# On-Screen-Display.net
KiCad netlist of a schematic drawn in Altium Designer
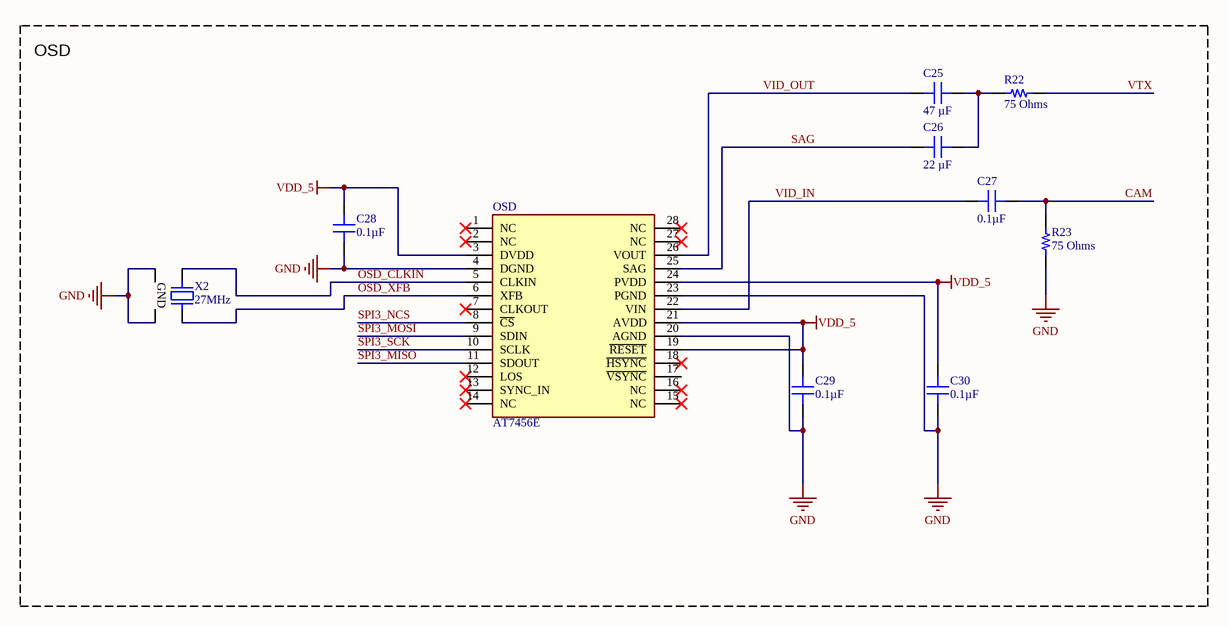
[diagram p0: On-Screen-Display.SchDoc]

(export (version "E")
  (design (tool "Eeschema 10.0.6"))
  (components
    (comp (ref "C25")
      (value "47 µF")
      (footprint "CAP 0603_1608")
      (description "CAP CER 47UF 6.3V X5R 0603")
      (fields
        (field (name "PART NUMBER") "GRM188R60J476ME15D")
        (field (name "MANUFACTURER") "Murata Electronics")
      )
      (libsource (lib "Celestial Altium Library - altium_library") (part "Capacitor"))
    )
    (comp (ref "C26")
      (value "22 µF")
      (footprint "CAP 0603_1608")
      (description "CAP CER 22UF 6.3V X5R 0603")
      (fields
        (field (name "PART NUMBER") "GRM186R60J226ME15D")
        (field (name "MANUFACTURER") "Murata Electronics")
      )
      (libsource (lib "Celestial Altium Library - altium_library") (part "Capacitor"))
    )
    (comp (ref "C27")
      (value "0.1µF")
      (footprint "CAP 0603_1608")
      (description "CAP CER 0.1UF 25V X7R 0603")
      (fields (field (name "PART NUMBER") "06033C104JAT4A") (field (name "MANUFACTURER") "AVX Corporation"))
      (libsource (lib "Celestial Altium Library - altium_library") (part "Capacitor"))
    )
    (comp (ref "C28")
      (value "0.1µF")
      (footprint "CAP 0603_1608")
      (description "CAP CER 0.1UF 25V X7R 0603")
      (fields (field (name "PART NUMBER") "06033C104JAT4A") (field (name "MANUFACTURER") "AVX Corporation"))
      (libsource (lib "Celestial Altium Library - altium_library") (part "Capacitor"))
    )
    (comp (ref "C29")
      (value "0.1µF")
      (footprint "CAP 0603_1608")
      (description "CAP CER 0.1UF 25V X7R 0603")
      (fields (field (name "PART NUMBER") "06033C104JAT4A") (field (name "MANUFACTURER") "AVX Corporation"))
      (libsource (lib "Celestial Altium Library - altium_library") (part "Capacitor"))
    )
    (comp (ref "C30")
      (value "0.1µF")
      (footprint "CAP 0603_1608")
      (description "CAP CER 0.1UF 25V X7R 0603")
      (fields (field (name "PART NUMBER") "06033C104JAT4A") (field (name "MANUFACTURER") "AVX Corporation"))
      (libsource (lib "Celestial Altium Library - altium_library") (part "Capacitor"))
    )
    (comp (ref "OSD")
      (value "AT7456E")
      (footprint "SamacSys:SOP65P640X120-29N")
      (description "Integrated Circuit")
      (libsource (lib "SamacSys") (part "AT7456E"))
    )
    (comp (ref "R22")
      (value "75 Ohms")
      (footprint "RES 0603_1608")
      (description "RES 75 OHM 1% 1/8W 0603")
      (fields
        (field (name "PART NUMBER") "RNCP0603FTD75R0")
        (field (name "MANUFACTURER") "Stackpole Electronics Inc")
      )
      (libsource (lib "Celestial Altium Library - altium_library") (part "Resistor"))
    )
    (comp (ref "R23")
      (value "75 Ohms")
      (footprint "RES 0603_1608")
      (description "RES 75 OHM 1% 1/8W 0603")
      (fields
        (field (name "PART NUMBER") "RNCP0603FTD75R0")
        (field (name "MANUFACTURER") "Stackpole Electronics Inc")
      )
      (libsource (lib "Celestial Altium Library - altium_library") (part "Resistor"))
    )
    (comp (ref "X2")
      (value "27MHz")
      (footprint "ABRACON ABM10")
      (description "CRYSTAL 27.0000MHZ 10PF SMD")
      (fields
        (field (name "PART NUMBER") "ABM10-27.000MHZ-D30-T3")
        (field (name "MANUFACTURER") "Abracon LLC")
      )
      (libsource (lib "Celestial Altium Library - altium_library") (part "Abracon Crystal ABM10"))
    )
  )
  (nets
    (net (code "1") (name "/CAM") (class "Default")
      (node (ref "C27") (pin "1") (pinfunction "1_1") (pintype "passive"))
      (node (ref "R23") (pin "2") (pinfunction "2_2") (pintype "passive"))
    )
    (net (code "2") (name "/OSD_CLKIN") (class "Default")
      (node (ref "OSD") (pin "5") (pinfunction "CLKIN_5") (pintype "passive"))
      (node (ref "X2") (pin "1") (pinfunction "1_1") (pintype "passive"))
    )
    (net (code "3") (name "/OSD_XFB") (class "Default")
      (node (ref "OSD") (pin "6") (pinfunction "XFB_6") (pintype "passive"))
      (node (ref "X2") (pin "3") (pinfunction "3_3") (pintype "passive"))
    )
    (net (code "4") (name "/SAG") (class "Default")
      (node (ref "C26") (pin "1") (pinfunction "1_1") (pintype "passive"))
      (node (ref "OSD") (pin "25") (pinfunction "SAG_25") (pintype "passive"))
    )
    (net (code "5") (name "/SPI3_MISO") (class "Default")
      (node (ref "OSD") (pin "11") (pinfunction "SDOUT_11") (pintype "passive"))
    )
    (net (code "6") (name "/SPI3_MOSI") (class "Default")
      (node (ref "OSD") (pin "9") (pinfunction "SDIN_9") (pintype "passive"))
    )
    (net (code "7") (name "/SPI3_NCS") (class "Default")
      (node (ref "OSD") (pin "8") (pinfunction "~{CS}_8") (pintype "passive"))
    )
    (net (code "8") (name "/SPI3_SCK") (class "Default")
      (node (ref "OSD") (pin "10") (pinfunction "SCLK_10") (pintype "passive"))
    )
    (net (code "9") (name "/VID_IN") (class "Default")
      (node (ref "C27") (pin "2") (pinfunction "2_2") (pintype "passive"))
      (node (ref "OSD") (pin "22") (pinfunction "VIN_22") (pintype "passive"))
    )
    (net (code "10") (name "/VID_OUT") (class "Default")
      (node (ref "C25") (pin "1") (pinfunction "1_1") (pintype "passive"))
      (node (ref "OSD") (pin "26") (pinfunction "VOUT_26") (pintype "passive"))
    )
    (net (code "11") (name "/VTX") (class "Default")
      (node (ref "R22") (pin "2") (pinfunction "2_2") (pintype "passive"))
    )
    (net (code "12") (name "GND") (class "Default")
      (node (ref "C28") (pin "1") (pinfunction "1_1") (pintype "passive"))
      (node (ref "C29") (pin "1") (pinfunction "1_1") (pintype "passive"))
      (node (ref "C30") (pin "1") (pinfunction "1_1") (pintype "passive"))
      (node (ref "OSD") (pin "20") (pinfunction "AGND_20") (pintype "passive"))
      (node (ref "OSD") (pin "23") (pinfunction "PGND_23") (pintype "passive"))
      (node (ref "OSD") (pin "4") (pinfunction "DGND_4") (pintype "passive"))
      (node (ref "R23") (pin "1") (pinfunction "1_1") (pintype "passive"))
      (node (ref "X2") (pin "2") (pinfunction "GND_2") (pintype "passive"))
      (node (ref "X2") (pin "4") (pinfunction "GND_4") (pintype "passive"))
    )
    (net (code "13") (name "Net-(C25-Pad2)") (class "Default")
      (node (ref "C25") (pin "2") (pinfunction "2_2") (pintype "passive"))
      (node (ref "C26") (pin "2") (pinfunction "2_2") (pintype "passive"))
      (node (ref "R22") (pin "1") (pinfunction "1_1") (pintype "passive"))
    )
    (net (code "14") (name "VDD_5") (class "Default")
      (node (ref "C28") (pin "2") (pinfunction "2_2") (pintype "passive"))
      (node (ref "C29") (pin "2") (pinfunction "2_2") (pintype "passive"))
      (node (ref "C30") (pin "2") (pinfunction "2_2") (pintype "passive"))
      (node (ref "OSD") (pin "19") (pinfunction "~{RESET}_19") (pintype "passive"))
      (node (ref "OSD") (pin "21") (pinfunction "AVDD_21") (pintype "passive"))
      (node (ref "OSD") (pin "24") (pinfunction "PVDD_24") (pintype "passive"))
      (node (ref "OSD") (pin "3") (pinfunction "DVDD_3") (pintype "passive"))
    )
    (net (code "15") (name "unconnected-(OSD-CLKOUT-Pad7)") (class "Default")
      (node (ref "OSD") (pin "7") (pinfunction "CLKOUT_7") (pintype "passive+no_connect"))
    )
    (net (code "16") (name "unconnected-(OSD-LOS-Pad12)") (class "Default")
      (node (ref "OSD") (pin "12") (pinfunction "LOS_12") (pintype "passive+no_connect"))
    )
    (net (code "17") (name "unconnected-(OSD-NC-Pad1)") (class "Default")
      (node (ref "OSD") (pin "1") (pinfunction "NC_1") (pintype "passive+no_connect"))
    )
    (net (code "18") (name "unconnected-(OSD-NC-Pad2)") (class "Default")
      (node (ref "OSD") (pin "2") (pinfunction "NC_2") (pintype "passive+no_connect"))
    )
    (net (code "19") (name "unconnected-(OSD-NC-Pad14)") (class "Default")
      (node (ref "OSD") (pin "14") (pinfunction "NC_14") (pintype "passive+no_connect"))
    )
    (net (code "20") (name "unconnected-(OSD-NC-Pad15)") (class "Default")
      (node (ref "OSD") (pin "15") (pinfunction "NC_15") (pintype "passive+no_connect"))
    )
    (net (code "21") (name "unconnected-(OSD-NC-Pad16)") (class "Default")
      (node (ref "OSD") (pin "16") (pinfunction "NC_16") (pintype "passive+no_connect"))
    )
    (net (code "22") (name "unconnected-(OSD-NC-Pad27)") (class "Default")
      (node (ref "OSD") (pin "27") (pinfunction "NC_27") (pintype "passive+no_connect"))
    )
    (net (code "23") (name "unconnected-(OSD-NC-Pad28)") (class "Default")
      (node (ref "OSD") (pin "28") (pinfunction "NC_28") (pintype "passive+no_connect"))
    )
    (net (code "24") (name "unconnected-(OSD-SYNC_IN-Pad13)") (class "Default")
      (node (ref "OSD") (pin "13") (pinfunction "SYNC_IN_13") (pintype "passive+no_connect"))
    )
    (net (code "25") (name "unconnected-(OSD-~{HSYNC}-Pad18)") (class "Default")
      (node (ref "OSD") (pin "18") (pinfunction "~{HSYNC}_18") (pintype "passive+no_connect"))
    )
    (net (code "26") (name "unconnected-(OSD-~{VSYNC}-Pad17)") (class "Default")
      (node (ref "OSD") (pin "17") (pinfunction "~{VSYNC}_17") (pintype "passive"))
    )
  )
)
